# E-21_DEBUG_RTC_USB_A_CAN.net
KiCad netlist of a schematic drawn in Altium Designer
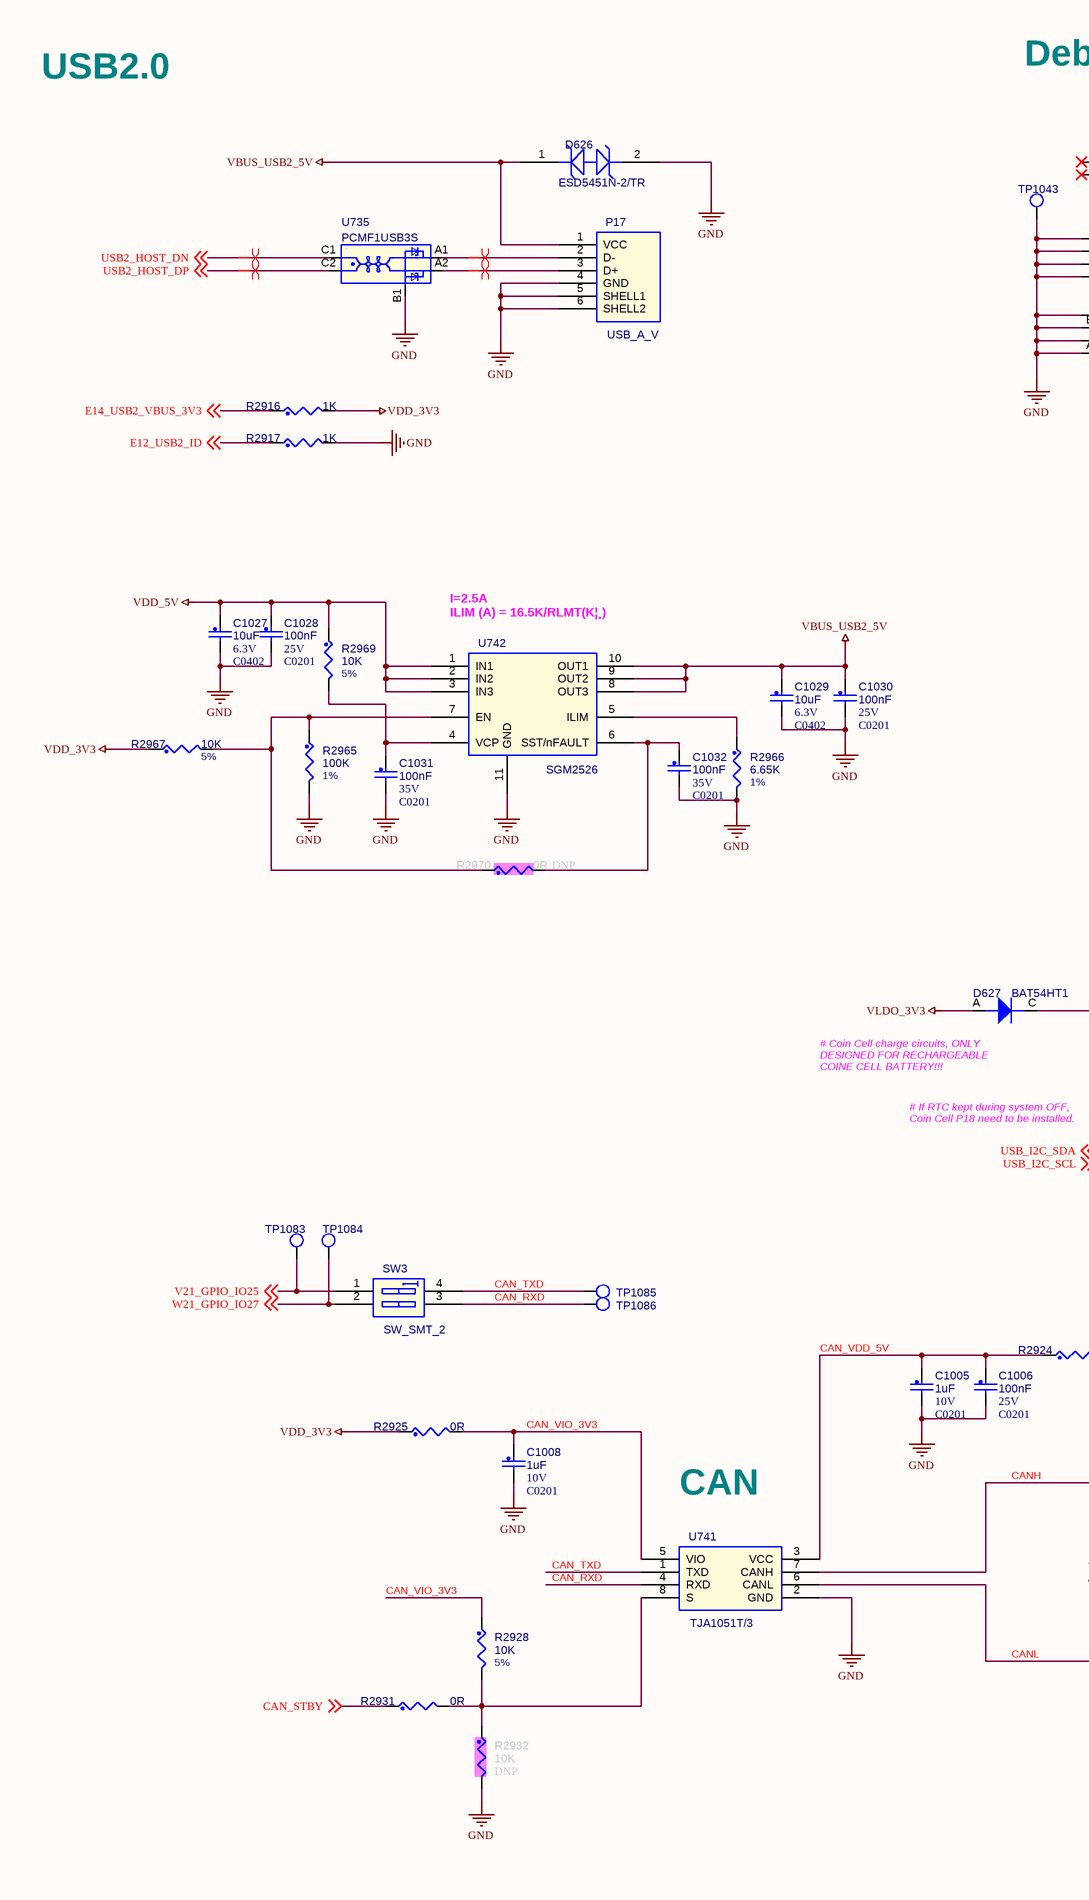
[diagram p0: E-21 DEBUG_RTC_USB A_CAN.SchDoc, left]
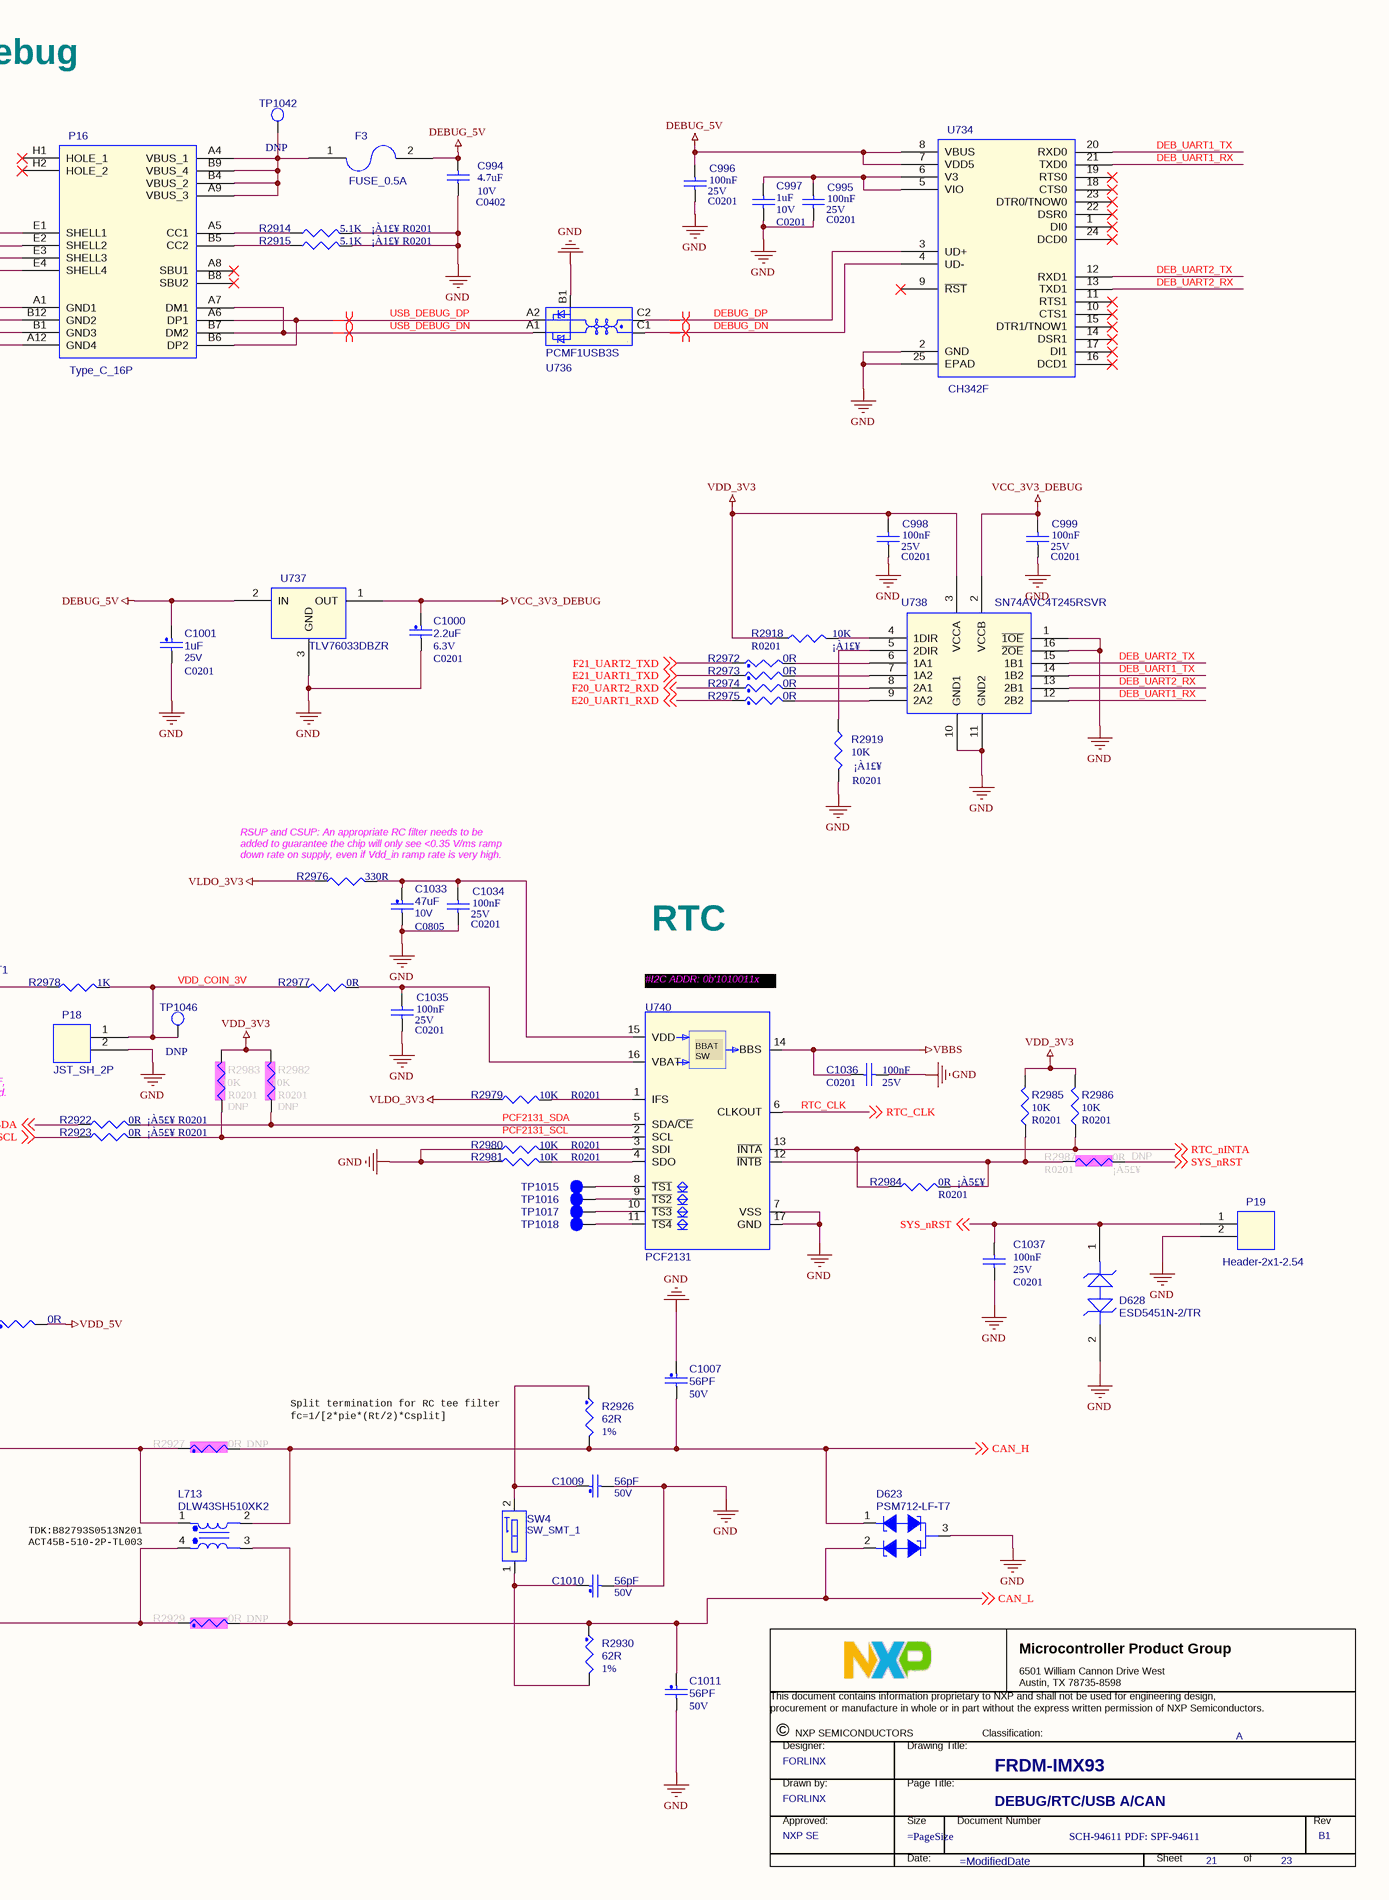
[diagram p1: E-21 DEBUG_RTC_USB A_CAN.SchDoc, right]

(export (version "E")
  (design (tool "Eeschema 10.0.6"))
  (components
    (comp (ref "C994")
      (value "4.7uF")
      (footprint "C0402")
      (description "0402,4.7uF,10V,+/-10%,X5R")
      (fields (field (name "VOLTAGE") "10V") (field (name "PCB FOOTPRINT") "C0402"))
      (libsource (lib "*") (part "C0603,4.7uF"))
    )
    (comp (ref "C995")
      (value "100nF")
      (footprint "C0201")
      (description "0201,100nF,25V,+/-10%,X5R")
      (fields (field (name "PCB FOOTPRINT") "C0201") (field (name "VOLTAGE") "25V"))
      (libsource (lib "*") (part "C0402,100nF,16V"))
    )
    (comp (ref "C996")
      (value "100nF")
      (footprint "C0201")
      (description "0201,100nF,25V,+/-10%,X5R")
      (fields (field (name "PCB FOOTPRINT") "C0201") (field (name "VOLTAGE") "25V"))
      (libsource (lib "*") (part "C0402,100nF,16V"))
    )
    (comp (ref "C997")
      (value "1uF")
      (footprint "C0201")
      (description "0201,1uF,10V,+/-20%,X5R")
      (fields (field (name "PCB FOOTPRINT") "C0201") (field (name "VOLTAGE") "10V"))
      (libsource (lib "*") (part "C0402,1uF,16V"))
    )
    (comp (ref "C998")
      (value "100nF")
      (footprint "C0201")
      (description "0201,100nF,25V,+/-10%,X5R")
      (fields (field (name "PCB FOOTPRINT") "C0201") (field (name "VOLTAGE") "25V"))
      (libsource (lib "*") (part "C0402,100nF,16V"))
    )
    (comp (ref "C999")
      (value "100nF")
      (footprint "C0201")
      (description "0201,100nF,25V,+/-10%,X5R")
      (fields (field (name "PCB FOOTPRINT") "C0201") (field (name "VOLTAGE") "25V"))
      (libsource (lib "*") (part "C0402,100nF,16V"))
    )
    (comp (ref "C1000")
      (value "2.2uF")
      (footprint "C0201")
      (description "0201,2.2uf,6.3V,+/-20%,X5R")
      (fields
        (field (name "TOLERANCE") "10%")
        (field (name "VOLTAGE") "6.3V")
        (field (name "PCB FOOTPRINT") "C0201")
      )
      (libsource (lib "*") (part "CAP_NP"))
    )
    (comp (ref "C1001")
      (value "1uF")
      (footprint "C0201")
      (description "0201,1uF,10V,+/-20%,X5R")
      (fields
        (field (name "RATED VOLTAGE") "25V")
        (field (name "TOLERANCE") "10%")
        (field (name "PCB FOOTPRINT") "C0201")
      )
      (libsource (lib "*") (part "CAP_NP"))
    )
    (comp (ref "C1005")
      (value "1uF")
      (footprint "C0201")
      (description "0201,1uF,10V,+/-20%,X5R")
      (fields
        (field (name "VOLTAGE") "10V")
        (field (name "TOLERANCE") "10%")
        (field (name "PCB FOOTPRINT") "C0201")
      )
      (libsource (lib "*") (part "CAP_NP"))
    )
    (comp (ref "C1006")
      (value "100nF")
      (footprint "C0201")
      (description "0201,100nF,25V,+/-10%,X5R")
      (fields
        (field (name "TOLERANCE") "10%")
        (field (name "VOLTAGE") "25V")
        (field (name "PCB FOOTPRINT") "C0201")
      )
      (libsource (lib "*") (part "CAP_NP"))
    )
    (comp (ref "C1007")
      (value "56PF")
      (footprint "C0402")
      (description "0402,56pF,50V,+/-5%,COG")
      (fields (field (name "TOLERANCE") "5%") (field (name "VOLTAGE") "50V"))
      (libsource (lib "*") (part "CAP_NP"))
    )
    (comp (ref "C1008")
      (value "1uF")
      (footprint "C0201")
      (description "0201,1uF,10V,+/-20%,X5R")
      (fields
        (field (name "VOLTAGE") "10V")
        (field (name "TOLERANCE") "10%")
        (field (name "PCB FOOTPRINT") "C0201")
      )
      (libsource (lib "*") (part "CAP_NP"))
    )
    (comp (ref "C1009")
      (value "56pF")
      (footprint "C0402")
      (description "0402,56pF,50V,+/-5%,COG")
      (fields (field (name "TOLERANCE") "5%") (field (name "VOLTAGE") "50V"))
      (libsource (lib "*") (part "CAP_NP"))
    )
    (comp (ref "C1010")
      (value "56pF")
      (footprint "C0402")
      (description "0402,56pF,50V,+/-5%,COG")
      (fields (field (name "VOLTAGE") "50V") (field (name "TOLERANCE") "5%"))
      (libsource (lib "*") (part "CAP_NP"))
    )
    (comp (ref "C1011")
      (value "56PF")
      (footprint "C0402")
      (description "0402,56pF,50V,+/-5%,COG")
      (fields (field (name "VOLTAGE") "50V") (field (name "TOLERANCE") "5%"))
      (libsource (lib "*") (part "CAP_NP"))
    )
    (comp (ref "C1027")
      (value "10uF")
      (footprint "C0402")
      (description "0402,10uF,6.3V,+/-20%,X5R")
      (fields
        (field (name "VOLTAGE") "6.3V")
        (field (name "TOLERANCE") "20%")
        (field (name "PCB FOOTPRINT") "C0402")
      )
      (libsource (lib "*") (part "CAP_NP"))
    )
    (comp (ref "C1028")
      (value "100nF")
      (footprint "C0201")
      (description "0201,100nF,25V,+/-10%,X5R")
      (fields
        (field (name "TOLERANCE") "10%")
        (field (name "VOLTAGE") "25V")
        (field (name "PCB FOOTPRINT") "C0201")
      )
      (libsource (lib "*") (part "CAP_NP"))
    )
    (comp (ref "C1029")
      (value "10uF")
      (footprint "C0402")
      (description "0402,10uF,6.3V,+/-20%,X5R")
      (fields
        (field (name "TOLERANCE") "20%")
        (field (name "VOLTAGE") "6.3V")
        (field (name "PCB FOOTPRINT") "C0402")
      )
      (libsource (lib "*") (part "CAP_NP"))
    )
    (comp (ref "C1030")
      (value "100nF")
      (footprint "C0201")
      (description "0201,100nF,25V,+/-10%,X5R")
      (fields
        (field (name "VOLTAGE") "25V")
        (field (name "TOLERANCE") "10%")
        (field (name "PCB FOOTPRINT") "C0201")
      )
      (libsource (lib "*") (part "CAP_NP"))
    )
    (comp (ref "C1031")
      (value "100nF")
      (footprint "C0201")
      (description "0201,100nF,25V,+/-10%,X5R")
      (fields
        (field (name "TOLERANCE") "10%")
        (field (name "VOLTAGE") "35V")
        (field (name "PCB FOOTPRINT") "C0201")
      )
      (libsource (lib "*") (part "CAP_NP"))
    )
    (comp (ref "C1032")
      (value "100nF")
      (footprint "C0201")
      (description "0201,100nF,25V,+/-10%,X5R")
      (fields
        (field (name "TOLERANCE") "10%")
        (field (name "VOLTAGE") "35V")
        (field (name "PCB FOOTPRINT") "C0201")
      )
      (libsource (lib "*") (part "CAP_NP"))
    )
    (comp (ref "C1033")
      (value "47uF")
      (footprint "C0805")
      (description "0805,47uF,10V,+/-20%,X5R")
      (fields
        (field (name "TOLERANCE") "10%")
        (field (name "RATED VOLTAGE") "10V")
        (field (name "PCB FOOTPRINT") "C0805")
      )
      (libsource (lib "*") (part "CAP_NP"))
    )
    (comp (ref "C1034")
      (value "100nF")
      (footprint "C0201")
      (description "0201,100nF,25V,+/-10%,X5R")
      (fields (field (name "PCB FOOTPRINT") "C0201") (field (name "VOLTAGE") "25V"))
      (libsource (lib "*") (part "C0402,100nF,16V"))
    )
    (comp (ref "C1035")
      (value "100nF")
      (footprint "C0201")
      (description "0201,100nF,25V,+/-10%,X5R")
      (fields (field (name "PCB FOOTPRINT") "C0201") (field (name "VOLTAGE") "25V"))
      (libsource (lib "*") (part "C0402,100nF,16V"))
    )
    (comp (ref "C1036")
      (value "100nF")
      (footprint "C0201")
      (description "0201,100nF,25V,+/-10%,X5R")
      (fields (field (name "PCB FOOTPRINT") "C0201") (field (name "VOLTAGE") "25V"))
      (libsource (lib "*") (part "C0402,100nF,16V"))
    )
    (comp (ref "C1037")
      (value "100nF")
      (footprint "C0201")
      (description "0201,100nF,25V,+/-10%,X5R")
      (fields (field (name "PCB FOOTPRINT") "C0201") (field (name "VOLTAGE") "25V"))
      (libsource (lib "*") (part "C0402,100nF,16V"))
    )
    (comp (ref "D623")
      (value "PSM712-LF-T7")
      (footprint "sot23_a")
      (description "PSM712-LF-T7,SOT-23-3")
      (libsource (lib "*") (part "ESD_DIODE_2LINE"))
    )
    (comp (ref "D626")
      (value "ESD5451N-2/TR")
      (footprint "0402TVS")
      (libsource (lib "*") (part "ESD5451N-2/TR"))
    )
    (comp (ref "D627")
      (value "BAT54HT1")
      (footprint "SOD323")
      (description "BAT54HT1G,SOD323")
      (libsource (lib "*") (part "DIODE"))
    )
    (comp (ref "D628")
      (value "ESD5451N-2/TR")
      (footprint "0402TVS")
      (libsource (lib "*") (part "ESD5451N-2/TR"))
    )
    (comp (ref "F3")
      (value "FUSE_0.5A")
      (footprint "F1206")
      (description "1206,0.5A/1A,13.2V")
      (libsource (lib "*") (part "FUSE_0.5A"))
    )
    (comp (ref "L713")
      (value "DLW43SH510XK2")
      (footprint "IND_DLW43")
      (description "IND CHK 51uH@1MHZ 230mA -30%/+50% 1812")
      (libsource (lib "*") (part "DLW43"))
    )
    (comp (ref "P16")
      (value "Type_C_16P")
      (footprint "TypeC_16P_S")
      (description "USB616FC-C2014216,USB2.0,type-c")
      (libsource (lib "*") (part "Type_C_16P"))
    )
    (comp (ref "P17")
      (value "USB_A_V")
      (footprint "USB_A_V")
      (description "USB2.0,Type A, female seat, single-layer, vertical lying, short body, length 14mm")
      (libsource (lib "*") (part "USB_A_V"))
    )
    (comp (ref "P18")
      (value "JST_SH_2P")
      (footprint "sh_2p")
      (description "A1001-02AB,Tin plating, busbar, 2P, 1mm spacing, vertical mounting")
      (libsource (lib "*") (part "JST_SH_2P"))
    )
    (comp (ref "P19")
      (value "Header-2x1-2.54")
      (footprint "Header_2x1_254")
      (description "XH,2P,2.54mm,S")
      (libsource (lib "*") (part "Header-2x1-2.54"))
    )
    (comp (ref "R2914")
      (value "5.1K")
      (footprint "R0201")
      (description "0201,5.1K,+/-1%")
      (fields (field (name "PCB FOOTPRINT") "R0201") (field (name "PRECISION") "±1％"))
      (libsource (lib "*") (part "R0402,4.7K"))
    )
    (comp (ref "R2915")
      (value "5.1K")
      (footprint "R0201")
      (description "0201,5.1K,+/-1%")
      (fields (field (name "PCB FOOTPRINT") "R0201") (field (name "PRECISION") "±1％"))
      (libsource (lib "*") (part "R0402,4.7K"))
    )
    (comp (ref "R2916")
      (value "1K")
      (footprint "R0201")
      (description "0201,1K,+/-1%")
      (fields (field (name "VOLTAGE") "1/16W") (field (name "TOLERANCE") "5%"))
      (libsource (lib "*") (part "RES"))
    )
    (comp (ref "R2917")
      (value "1K")
      (footprint "R0201")
      (description "0201,1K,+/-1%")
      (fields (field (name "VOLTAGE") "1/16W") (field (name "TOLERANCE") "5%"))
      (libsource (lib "*") (part "RES"))
    )
    (comp (ref "R2918")
      (value "10K")
      (footprint "R0201")
      (description "0201,10K,+/-5%")
      (fields (field (name "PRECISION") "±1％") (field (name "PCB FOOTPRINT") "R0201"))
      (libsource (lib "*") (part "R0402,10K"))
    )
    (comp (ref "R2919")
      (value "10K")
      (footprint "R0201")
      (description "0201,10K,+/-5%")
      (fields (field (name "PRECISION") "±1％") (field (name "PCB FOOTPRINT") "R0201"))
      (libsource (lib "*") (part "R0402,10K"))
    )
    (comp (ref "R2922")
      (value "0R")
      (footprint "R0201")
      (description "0201,0Ohm,+/-5%")
      (fields (field (name "PRECISION") "±5％") (field (name "PCB FOOTPRINT") "R0201"))
      (libsource (lib "*") (part "R0402,0R"))
    )
    (comp (ref "R2923")
      (value "0R")
      (footprint "R0201")
      (description "0201,0Ohm,+/-5%")
      (fields (field (name "PRECISION") "±5％") (field (name "PCB FOOTPRINT") "R0201"))
      (libsource (lib "*") (part "R0402,0R"))
    )
    (comp (ref "R2924")
      (value "0R")
      (footprint "R0402")
      (description "0402,0Ohm,+/-1%")
      (fields (field (name "TOLERANCE") "5%") (field (name "VOLTAGE") "1/16W"))
      (libsource (lib "*") (part "RES"))
    )
    (comp (ref "R2925")
      (value "0R")
      (footprint "R0402")
      (description "0402,0Ohm,+/-1%")
      (fields (field (name "VOLTAGE") "1/16W") (field (name "TOLERANCE") "5%"))
      (libsource (lib "*") (part "RES"))
    )
    (comp (ref "R2926")
      (value "62R")
      (footprint "R0603")
      (description "0603,62Ohm,+/-5%")
      (fields (field (name "TOLERANCE") "1%"))
      (libsource (lib "*") (part "RES"))
    )
    (comp (ref "R2927")
      (value "0R")
      (footprint "R0402")
      (description "0402,0Ohm,+/-1%")
      (fields
        (field (name "ASSY_OPT") "DNP")
        (field (name "TOLERANCE") "5%")
        (field (name "VOLTAGE") "1/16W")
      )
      (libsource (lib "*") (part "RES"))
    )
    (comp (ref "R2928")
      (value "10K")
      (footprint "R0201")
      (description "0201,10K,+/-5%")
      (fields (field (name "TOLERANCE") "5%"))
      (libsource (lib "*") (part "RES"))
    )
    (comp (ref "R2929")
      (value "0R")
      (footprint "R0402")
      (description "0402,0Ohm,+/-1%")
      (fields
        (field (name "ASSY_OPT") "DNP")
        (field (name "TOLERANCE") "5%")
        (field (name "VOLTAGE") "1/16W")
      )
      (libsource (lib "*") (part "RES"))
    )
    (comp (ref "R2930")
      (value "62R")
      (footprint "R0603")
      (description "0603,62Ohm,+/-5%")
      (fields (field (name "TOLERANCE") "1%"))
      (libsource (lib "*") (part "RES"))
    )
    (comp (ref "R2931")
      (value "0R")
      (footprint "R0201")
      (description "0201,0Ohm,+/-5%")
      (fields (field (name "VOLTAGE") "1/16W") (field (name "TOLERANCE") "5%"))
      (libsource (lib "*") (part "RES"))
    )
    (comp (ref "R2932")
      (value "10K")
      (footprint "R0201")
      (description "0201,10K,+/-5%")
      (fields (field (name "ASSY_OPT") "DNP") (field (name "TOLERANCE") "5%"))
      (libsource (lib "*") (part "RES"))
    )
    (comp (ref "R2965")
      (value "100K")
      (footprint "R0201")
      (description "0201,100K,+/-1%")
      (fields (field (name "TOLERANCE") "1%"))
      (libsource (lib "*") (part "RES"))
    )
    (comp (ref "R2966")
      (value "6.65K")
      (footprint "R0402")
      (description "0402,6.65K,+/-1%")
      (fields (field (name "TOLERANCE") "1%"))
      (libsource (lib "*") (part "RES"))
    )
    (comp (ref "R2967")
      (value "10K")
      (footprint "R0201")
      (description "0201,10K,+/-5%")
      (fields (field (name "TOLERANCE") "5%"))
      (libsource (lib "*") (part "RES"))
    )
    (comp (ref "R2969")
      (value "10K")
      (footprint "R0201")
      (description "0201,10K,+/-5%")
      (fields (field (name "TOLERANCE") "5%"))
      (libsource (lib "*") (part "RES"))
    )
    (comp (ref "R2970")
      (value "0R")
      (footprint "R0201")
      (description "0201,0Ohm,+/-5%")
      (fields
        (field (name "ASSY_OPT") "DNP")
        (field (name "VOLTAGE") "1/16W")
        (field (name "TOLERANCE") "5%")
      )
      (libsource (lib "*") (part "RES"))
    )
    (comp (ref "R2972")
      (value "0R")
      (footprint "R0201")
      (description "0201,0Ohm,+/-5%")
      (fields (field (name "TOLERANCE") "5%") (field (name "VOLTAGE") "1/16W"))
      (libsource (lib "*") (part "RES"))
    )
    (comp (ref "R2973")
      (value "0R")
      (footprint "R0201")
      (description "0201,0Ohm,+/-5%")
      (fields (field (name "TOLERANCE") "5%") (field (name "VOLTAGE") "1/16W"))
      (libsource (lib "*") (part "RES"))
    )
    (comp (ref "R2974")
      (value "0R")
      (footprint "R0201")
      (description "0201,0Ohm,+/-5%")
      (fields (field (name "TOLERANCE") "5%") (field (name "VOLTAGE") "1/16W"))
      (libsource (lib "*") (part "RES"))
    )
    (comp (ref "R2975")
      (value "0R")
      (footprint "R0201")
      (description "0201,0Ohm,+/-5%")
      (fields (field (name "TOLERANCE") "5%") (field (name "VOLTAGE") "1/16W"))
      (libsource (lib "*") (part "RES"))
    )
    (comp (ref "R2976")
      (value "330R")
      (footprint "R0402")
      (description "0402,330Ohm,+/-1%")
      (libsource (lib "*") (part "R0402,10K"))
    )
    (comp (ref "R2977")
      (value "0R")
      (footprint "R0402")
      (description "0402,0Ohm,+/-1%")
      (libsource (lib "*") (part "R0402,10K"))
    )
    (comp (ref "R2978")
      (value "1K")
      (footprint "R0402")
      (description "0402,1K,+/-1%")
      (libsource (lib "*") (part "R0402,10K"))
    )
    (comp (ref "R2979")
      (value "10K")
      (footprint "R0201")
      (description "0201,10K,+/-5%")
      (fields (field (name "PCB FOOTPRINT") "R0201"))
      (libsource (lib "*") (part "R0402,10K"))
    )
    (comp (ref "R2980")
      (value "10K")
      (footprint "R0201")
      (description "0201,10K,+/-5%")
      (fields (field (name "PCB FOOTPRINT") "R0201"))
      (libsource (lib "*") (part "R0402,10K"))
    )
    (comp (ref "R2981")
      (value "10K")
      (footprint "R0201")
      (description "0201,10K,+/-5%")
      (fields (field (name "PCB FOOTPRINT") "R0201"))
      (libsource (lib "*") (part "R0402,10K"))
    )
    (comp (ref "R2982")
      (value "10K")
      (footprint "R0201")
      (description "0201,10K,+/-5%")
      (fields (field (name "PCB FOOTPRINT") "R0201") (field (name "ASSY_OPT") "DNP"))
      (libsource (lib "*") (part "R0402,10K"))
    )
    (comp (ref "R2983")
      (value "10K")
      (footprint "R0201")
      (description "0201,10K,+/-5%")
      (fields (field (name "PCB FOOTPRINT") "R0201") (field (name "ASSY_OPT") "DNP"))
      (libsource (lib "*") (part "R0402,10K"))
    )
    (comp (ref "R2984")
      (value "0R")
      (footprint "R0201")
      (description "0201,0Ohm,+/-5%")
      (fields (field (name "PRECISION") "±5％") (field (name "PCB FOOTPRINT") "R0201"))
      (libsource (lib "*") (part "R0402,0R"))
    )
    (comp (ref "R2985")
      (value "10K")
      (footprint "R0201")
      (description "0201,10K,+/-5%")
      (fields (field (name "PCB FOOTPRINT") "R0201"))
      (libsource (lib "*") (part "R0402,10K"))
    )
    (comp (ref "R2986")
      (value "10K")
      (footprint "R0201")
      (description "0201,10K,+/-5%")
      (fields (field (name "PCB FOOTPRINT") "R0201"))
      (libsource (lib "*") (part "R0402,10K"))
    )
    (comp (ref "R2987")
      (value "0R")
      (footprint "R0201")
      (description "0201,0Ohm,+/-5%")
      (fields
        (field (name "PRECISION") "±5％")
        (field (name "PCB FOOTPRINT") "R0201")
        (field (name "ASSY_OPT") "DNP")
      )
      (libsource (lib "*") (part "R0402,0R"))
    )
    (comp (ref "SW3")
      (value "SW_SMT_2")
      (footprint "SW_SMT_4")
      (description "2bit,4P,1.27mm,black")
      (libsource (lib "*") (part "SW_SMT_1"))
    )
    (comp (ref "SW4")
      (value "SW_SMT_1")
      (footprint "sw_2p8x5p4_sm")
      (description "1bit,2P,1.27mm,black")
      (libsource (lib "*") (part "SW-SPST_A"))
    )
    (comp (ref "TP1015")
      (value "TPAD_015")
      (footprint "tpad_015")
      (description "no part to order")
      (libsource (lib "*") (part "TESTLOOP"))
    )
    (comp (ref "TP1016")
      (value "TPAD_015")
      (footprint "tpad_015")
      (description "no part to order")
      (libsource (lib "*") (part "TESTLOOP"))
    )
    (comp (ref "TP1017")
      (value "TPAD_015")
      (footprint "tpad_015")
      (description "no part to order")
      (libsource (lib "*") (part "TESTLOOP"))
    )
    (comp (ref "TP1018")
      (value "TPAD_015")
      (footprint "tpad_015")
      (description "no part to order")
      (libsource (lib "*") (part "TESTLOOP"))
    )
    (comp (ref "TP1042")
      (value "TPAD_020")
      (footprint "tpad_020")
      (description "no part to order")
      (fields (field (name "ASSY_OPT") "DNP"))
      (libsource (lib "*") (part "T POINT R"))
    )
    (comp (ref "TP1043")
      (value "TPAD_020")
      (footprint "tpad_020")
      (description "no part to order")
      (libsource (lib "*") (part "T POINT R"))
    )
    (comp (ref "TP1046")
      (value "TPAD_020")
      (footprint "tpad_020")
      (description "no part to order")
      (fields (field (name "ASSY_OPT") "DNP"))
      (libsource (lib "*") (part "T POINT R"))
    )
    (comp (ref "TP1083")
      (value "TPAD_020")
      (footprint "tpad_020")
      (description "no part to order")
      (libsource (lib "*") (part "T POINT R"))
    )
    (comp (ref "TP1084")
      (value "TPAD_020")
      (footprint "tpad_020")
      (description "no part to order")
      (libsource (lib "*") (part "T POINT R"))
    )
    (comp (ref "TP1085")
      (value "TPAD_020")
      (footprint "tpad_020")
      (description "no part to order")
      (libsource (lib "*") (part "T POINT R"))
    )
    (comp (ref "TP1086")
      (value "TPAD_020")
      (footprint "tpad_020")
      (description "no part to order")
      (libsource (lib "*") (part "T POINT R"))
    )
    (comp (ref "U734") (value "CH342F") (footprint "QFN24P_0_5") (libsource (lib "*") (part "CH342F")))
    (comp (ref "U735")
      (value "PCMF1USB3S")
      (footprint "wlcsp5_0p4_0p82x1p22")
      (description "IC EMI FILTER ESD PROTECTION 15kV/LINE WLCSP5")
      (fields
        (field (name "MANUFACTURER PART NUMBER") "PESD1USB30")
        (field (name "MANUFACTURER") "NXP Semiconductors")
      )
      (libsource (lib "*") (part "PESD1USB30_5P"))
    )
    (comp (ref "U736")
      (value "PCMF1USB3S")
      (footprint "wlcsp5_0p4_0p82x1p22")
      (description "IC EMI FILTER ESD PROTECTION 15kV/LINE WLCSP5")
      (fields
        (field (name "MANUFACTURER PART NUMBER") "PESD1USB30")
        (field (name "MANUFACTURER") "NXP Semiconductors")
      )
      (libsource (lib "") (part "PESD1USB30_5P_1"))
    )
    (comp (ref "U737")
      (value "TLV76033DBZR")
      (footprint "sot23_a")
      (libsource (lib "*") (part "SGM2034-3_1.3YN3G"))
    )
    (comp (ref "U738")
      (value "SN74AVC4T245RSVR")
      (footprint "UQFN16_26x18")
      (description "SN74AVC4T245RSVR,UQFN16_2.6x1.8mm")
      (libsource (lib "*") (part "SN74AVC4T245RSVR"))
    )
    (comp (ref "U740")
      (value "PCF2131")
      (footprint "so16_0p5_3p5x4p5_mm")
      (description "PCF2131TF,HLSON16,Nano-power highly accurate RTC with integrated quartz crystal")
      (libsource (lib "*") (part "PCF2131_4"))
    )
    (comp (ref "U741")
      (value "TJA1051T/3")
      (footprint "SOP8_1_27")
      (description "TJA1051T/3,SO8")
      (libsource (lib "*") (part "TJA1051T/3"))
    )
    (comp (ref "U742")
      (value "SGM2526")
      (footprint "tdfn_3x3_10l")
      (description "SGM2526YTD10G/TR,TDFN-3x3-10L,-40+C~85+C,Imax 5A")
      (libsource (lib "*") (part "SGM2526_3"))
    )
  )
  (nets
    (net (code "1") (name "/CANH") (class "Default")
      (node (ref "L713") (pin "1") (pinfunction "1_1") (pintype "passive"))
      (node (ref "R2927") (pin "1") (pinfunction "1_1") (pintype "passive"))
      (node (ref "U741") (pin "7") (pinfunction "CANH_7") (pintype "passive"))
    )
    (net (code "2") (name "/CANL") (class "Default")
      (node (ref "L713") (pin "4") (pinfunction "4_4") (pintype "passive"))
      (node (ref "R2929") (pin "1") (pinfunction "1_1") (pintype "passive"))
      (node (ref "U741") (pin "6") (pinfunction "CANL_6") (pintype "passive"))
    )
    (net (code "3") (name "/CAN_RXD") (class "Default")
      (node (ref "SW3") (pin "3") (pinfunction "3_3") (pintype "passive"))
      (node (ref "TP1086") (pin "1") (pinfunction "TP_1") (pintype "passive"))
      (node (ref "U741") (pin "4") (pinfunction "RXD_4") (pintype "passive"))
    )
    (net (code "4") (name "/CAN_TXD") (class "Default")
      (node (ref "SW3") (pin "4") (pinfunction "4_4") (pintype "passive"))
      (node (ref "TP1085") (pin "1") (pinfunction "TP_1") (pintype "passive"))
      (node (ref "U741") (pin "1") (pinfunction "TXD_1") (pintype "passive"))
    )
    (net (code "5") (name "/CAN_VDD_5V") (class "Default")
      (node (ref "C1005") (pin "1") (pinfunction "1_1") (pintype "passive"))
      (node (ref "C1006") (pin "1") (pinfunction "1_1") (pintype "passive"))
      (node (ref "R2924") (pin "1") (pinfunction "1_1") (pintype "passive"))
      (node (ref "U741") (pin "3") (pinfunction "VCC_3") (pintype "passive"))
    )
    (net (code "6") (name "/CAN_VIO_3V3") (class "Default")
      (node (ref "C1008") (pin "1") (pinfunction "1_1") (pintype "passive"))
      (node (ref "R2925") (pin "2") (pinfunction "2_2") (pintype "passive"))
      (node (ref "R2928") (pin "1") (pinfunction "1_1") (pintype "passive"))
      (node (ref "U741") (pin "5") (pinfunction "VIO_5") (pintype "passive"))
    )
    (net (code "7") (name "/DEBUG_DN") (class "Default")
      (node (ref "U734") (pin "4") (pinfunction "UD-_4") (pintype "passive"))
      (node (ref "U736") (pin "C1") (pinfunction "CH1_OUT+_C1") (pintype "bidirectional"))
    )
    (net (code "8") (name "/DEBUG_DP") (class "Default")
      (node (ref "U734") (pin "3") (pinfunction "UD+_3") (pintype "passive"))
      (node (ref "U736") (pin "C2") (pinfunction "CH1_OUT-_C2") (pintype "bidirectional"))
    )
    (net (code "9") (name "/DEB_UART1_RX") (class "Default")
      (node (ref "U734") (pin "21") (pinfunction "TXD0_21") (pintype "passive"))
      (node (ref "U738") (pin "12") (pinfunction "2B2_12") (pintype "passive"))
    )
    (net (code "10") (name "/DEB_UART1_TX") (class "Default")
      (node (ref "U734") (pin "20") (pinfunction "RXD0_20") (pintype "passive"))
      (node (ref "U738") (pin "14") (pinfunction "1B2_14") (pintype "passive"))
    )
    (net (code "11") (name "/DEB_UART2_RX") (class "Default")
      (node (ref "U734") (pin "13") (pinfunction "TXD1_13") (pintype "passive"))
      (node (ref "U738") (pin "13") (pinfunction "2B1_13") (pintype "passive"))
    )
    (net (code "12") (name "/DEB_UART2_TX") (class "Default")
      (node (ref "U734") (pin "12") (pinfunction "RXD1_12") (pintype "passive"))
      (node (ref "U738") (pin "15") (pinfunction "1B1_15") (pintype "passive"))
    )
    (net (code "13") (name "/PCF2131_SCL") (class "Default")
      (node (ref "R2923") (pin "2") (pinfunction "2_2") (pintype "passive"))
      (node (ref "R2983") (pin "1") (pinfunction "1_1") (pintype "passive"))
      (node (ref "U740") (pin "2") (pinfunction "SCL_2") (pintype "passive"))
    )
    (net (code "14") (name "/PCF2131_SDA") (class "Default")
      (node (ref "R2922") (pin "2") (pinfunction "2_2") (pintype "passive"))
      (node (ref "R2982") (pin "1") (pinfunction "1_1") (pintype "passive"))
      (node (ref "U740") (pin "5") (pinfunction "SDA/~{CE}_5") (pintype "passive"))
    )
    (net (code "15") (name "/USB_DEBUG_DN") (class "Default")
      (node (ref "P16") (pin "A7") (pinfunction "DM1_A7") (pintype "passive"))
      (node (ref "P16") (pin "B7") (pinfunction "DM2_B7") (pintype "passive"))
      (node (ref "U736") (pin "A1") (pinfunction "CH1_IN+_A1") (pintype "bidirectional"))
    )
    (net (code "16") (name "/USB_DEBUG_DP") (class "Default")
      (node (ref "P16") (pin "A6") (pinfunction "DP1_A6") (pintype "passive"))
      (node (ref "P16") (pin "B6") (pinfunction "DP2_B6") (pintype "passive"))
      (node (ref "U736") (pin "A2") (pinfunction "CH1_IN-_A2") (pintype "bidirectional"))
    )
    (net (code "17") (name "/VDD_COIN_3V") (class "Default")
      (node (ref "P18") (pin "1") (pinfunction "1_1") (pintype "passive"))
      (node (ref "R2977") (pin "1") (pinfunction "1_1") (pintype "passive"))
      (node (ref "R2978") (pin "2") (pinfunction "2_2") (pintype "passive"))
      (node (ref "TP1046") (pin "1") (pinfunction "TP_1") (pintype "passive"))
    )
    (net (code "18") (name "CAN_H") (class "Default")
      (node (ref "C1007") (pin "2") (pinfunction "2_2") (pintype "passive"))
      (node (ref "D623") (pin "1") (pinfunction "CATHODE1_1") (pintype "passive"))
      (node (ref "L713") (pin "2") (pinfunction "2_2") (pintype "passive"))
      (node (ref "R2926") (pin "2") (pinfunction "2_2") (pintype "passive"))
      (node (ref "R2927") (pin "2") (pinfunction "2_2") (pintype "passive"))
    )
    (net (code "19") (name "CAN_L") (class "Default")
      (node (ref "C1011") (pin "1") (pinfunction "1_1") (pintype "passive"))
      (node (ref "D623") (pin "2") (pinfunction "CATHODE2_2") (pintype "passive"))
      (node (ref "L713") (pin "3") (pinfunction "3_3") (pintype "passive"))
      (node (ref "R2929") (pin "2") (pinfunction "2_2") (pintype "passive"))
      (node (ref "R2930") (pin "1") (pinfunction "1_1") (pintype "passive"))
    )
    (net (code "20") (name "CAN_STBY") (class "Default")
      (node (ref "R2931") (pin "1") (pinfunction "1_1") (pintype "passive"))
    )
    (net (code "21") (name "DEBUG_5V") (class "Default")
      (node (ref "C1001") (pin "1") (pinfunction "1_1") (pintype "passive"))
      (node (ref "C994") (pin "1") (pinfunction "1_1") (pintype "passive"))
      (node (ref "C996") (pin "1") (pinfunction "1_1") (pintype "passive"))
      (node (ref "F3") (pin "2") (pinfunction "2_2") (pintype "passive"))
      (node (ref "U734") (pin "7") (pinfunction "VDD5_7") (pintype "passive"))
      (node (ref "U734") (pin "8") (pinfunction "VBUS_8") (pintype "passive"))
      (node (ref "U737") (pin "2") (pinfunction "IN_2") (pintype "passive"))
    )
    (net (code "22") (name "E12_USB2_ID") (class "Default")
      (node (ref "R2917") (pin "1") (pinfunction "1_1") (pintype "passive"))
    )
    (net (code "23") (name "E14_USB2_VBUS_3V3") (class "Default")
      (node (ref "R2916") (pin "1") (pinfunction "1_1") (pintype "passive"))
    )
    (net (code "24") (name "E20_UART1_RXD") (class "Default")
      (node (ref "R2975") (pin "1") (pinfunction "1_1") (pintype "passive"))
    )
    (net (code "25") (name "E21_UART1_TXD") (class "Default")
      (node (ref "R2973") (pin "1") (pinfunction "1_1") (pintype "passive"))
    )
    (net (code "26") (name "F20_UART2_RXD") (class "Default")
      (node (ref "R2974") (pin "1") (pinfunction "1_1") (pintype "passive"))
    )
    (net (code "27") (name "F21_UART2_TXD") (class "Default")
      (node (ref "R2972") (pin "1") (pinfunction "1_1") (pintype "passive"))
    )
    (net (code "28") (name "GND") (class "Default")
      (node (ref "C1000") (pin "2") (pinfunction "2_2") (pintype "passive"))
      (node (ref "C1001") (pin "2") (pinfunction "2_2") (pintype "passive"))
      (node (ref "C1005") (pin "2") (pinfunction "2_2") (pintype "passive"))
      (node (ref "C1006") (pin "2") (pinfunction "2_2") (pintype "passive"))
      (node (ref "C1007") (pin "1") (pinfunction "1_1") (pintype "passive"))
      (node (ref "C1008") (pin "2") (pinfunction "2_2") (pintype "passive"))
      (node (ref "C1009") (pin "2") (pinfunction "2_2") (pintype "passive"))
      (node (ref "C1010") (pin "2") (pinfunction "2_2") (pintype "passive"))
      (node (ref "C1011") (pin "2") (pinfunction "2_2") (pintype "passive"))
      (node (ref "C1027") (pin "2") (pinfunction "2_2") (pintype "passive"))
      (node (ref "C1028") (pin "2") (pinfunction "2_2") (pintype "passive"))
      (node (ref "C1029") (pin "2") (pinfunction "2_2") (pintype "passive"))
      (node (ref "C1030") (pin "2") (pinfunction "2_2") (pintype "passive"))
      (node (ref "C1031") (pin "2") (pinfunction "2_2") (pintype "passive"))
      (node (ref "C1032") (pin "2") (pinfunction "2_2") (pintype "passive"))
      (node (ref "C1033") (pin "2") (pinfunction "2_2") (pintype "passive"))
      (node (ref "C1034") (pin "2") (pinfunction "2_2") (pintype "passive"))
      (node (ref "C1035") (pin "2") (pinfunction "2_2") (pintype "passive"))
      (node (ref "C1036") (pin "2") (pinfunction "2_2") (pintype "passive"))
      (node (ref "C1037") (pin "1") (pinfunction "1_1") (pintype "passive"))
      (node (ref "C994") (pin "2") (pinfunction "2_2") (pintype "passive"))
      (node (ref "C995") (pin "2") (pinfunction "2_2") (pintype "passive"))
      (node (ref "C996") (pin "2") (pinfunction "2_2") (pintype "passive"))
      (node (ref "C997") (pin "2") (pinfunction "2_2") (pintype "passive"))
      (node (ref "C998") (pin "2") (pinfunction "2_2") (pintype "passive"))
      (node (ref "C999") (pin "2") (pinfunction "2_2") (pintype "passive"))
      (node (ref "D623") (pin "3") (pinfunction "COM_CATHODE_3") (pintype "passive"))
      (node (ref "D626") (pin "2") (pinfunction "2_2") (pintype "passive"))
      (node (ref "D628") (pin "2") (pinfunction "2_2") (pintype "passive"))
      (node (ref "P16") (pin "A1") (pinfunction "GND1_A1") (pintype "passive"))
      (node (ref "P16") (pin "A12") (pinfunction "GND4_A12") (pintype "passive"))
      (node (ref "P16") (pin "B1") (pinfunction "GND3_B1") (pintype "passive"))
      (node (ref "P16") (pin "B12") (pinfunction "GND2_B12") (pintype "passive"))
      (node (ref "P16") (pin "E1") (pinfunction "SHELL1_E1") (pintype "passive"))
      (node (ref "P16") (pin "E2") (pinfunction "SHELL2_E2") (pintype "passive"))
      (node (ref "P16") (pin "E3") (pinfunction "SHELL3_E3") (pintype "passive"))
      (node (ref "P16") (pin "E4") (pinfunction "SHELL4_E4") (pintype "passive"))
      (node (ref "P17") (pin "4") (pinfunction "GND_4") (pintype "passive"))
      (node (ref "P17") (pin "5") (pinfunction "SHELL1_5") (pintype "passive"))
      (node (ref "P17") (pin "6") (pinfunction "SHELL2_6") (pintype "passive"))
      (node (ref "P18") (pin "2") (pinfunction "2_2") (pintype "passive"))
      (node (ref "P19") (pin "2") (pinfunction "2_2") (pintype "passive"))
      (node (ref "R2914") (pin "2") (pinfunction "2_2") (pintype "passive"))
      (node (ref "R2915") (pin "2") (pinfunction "2_2") (pintype "passive"))
      (node (ref "R2917") (pin "2") (pinfunction "2_2") (pintype "passive"))
      (node (ref "R2919") (pin "2") (pinfunction "2_2") (pintype "passive"))
      (node (ref "R2932") (pin "2") (pinfunction "2_2") (pintype "passive"))
      (node (ref "R2965") (pin "2") (pinfunction "2_2") (pintype "passive"))
      (node (ref "R2966") (pin "2") (pinfunction "2_2") (pintype "passive"))
      (node (ref "R2980") (pin "1") (pinfunction "1_1") (pintype "passive"))
      (node (ref "R2981") (pin "1") (pinfunction "1_1") (pintype "passive"))
      (node (ref "TP1043") (pin "1") (pinfunction "TP_1") (pintype "passive"))
      (node (ref "U734") (pin "2") (pinfunction "GND_2") (pintype "passive"))
      (node (ref "U734") (pin "25") (pinfunction "EPAD_25") (pintype "passive"))
      (node (ref "U735") (pin "B1") (pinfunction "GND_B1") (pintype "power_in"))
      (node (ref "U736") (pin "B1") (pinfunction "GND_B1") (pintype "power_in"))
      (node (ref "U737") (pin "3") (pinfunction "GND_3") (pintype "passive"))
      (node (ref "U738") (pin "1") (pinfunction "~{1OE}_1") (pintype "passive"))
      (node (ref "U738") (pin "10") (pinfunction "GND1_10") (pintype "passive"))
      (node (ref "U738") (pin "11") (pinfunction "GND2_11") (pintype "passive"))
      (node (ref "U738") (pin "16") (pinfunction "~{2OE}_16") (pintype "passive"))
      (node (ref "U740") (pin "17") (pinfunction "GND_17") (pintype "power_in"))
      (node (ref "U740") (pin "7") (pinfunction "VSS_7") (pintype "power_in"))
      (node (ref "U741") (pin "2") (pinfunction "GND_2") (pintype "passive"))
      (node (ref "U742") (pin "11") (pinfunction "GND_11") (pintype "passive"))
    )
    (net (code "29") (name "Net-(D627-CATHODE)") (class "Default")
      (node (ref "D627") (pin "C") (pinfunction "CATHODE_C") (pintype "passive"))
      (node (ref "R2978") (pin "1") (pinfunction "1_1") (pintype "passive"))
    )
    (net (code "30") (name "Net-(P16-CC1)") (class "Default")
      (node (ref "P16") (pin "A5") (pinfunction "CC1_A5") (pintype "passive"))
      (node (ref "R2914") (pin "1") (pinfunction "1_1") (pintype "passive"))
    )
    (net (code "31") (name "Net-(P16-CC2)") (class "Default")
      (node (ref "P16") (pin "B5") (pinfunction "CC2_B5") (pintype "passive"))
      (node (ref "R2915") (pin "1") (pinfunction "1_1") (pintype "passive"))
    )
    (net (code "32") (name "Net-(P16-VBUS_1)") (class "Default")
      (node (ref "F3") (pin "1") (pinfunction "1_1") (pintype "passive"))
      (node (ref "P16") (pin "A4") (pinfunction "VBUS_1_A4") (pintype "passive"))
      (node (ref "P16") (pin "A9") (pinfunction "VBUS_3_A9") (pintype "passive"))
      (node (ref "P16") (pin "B4") (pinfunction "VBUS_2_B4") (pintype "passive"))
      (node (ref "P16") (pin "B9") (pinfunction "VBUS_4_B9") (pintype "passive"))
      (node (ref "TP1042") (pin "1") (pinfunction "TP_1") (pintype "passive"))
    )
    (net (code "33") (name "Net-(P17-D+)") (class "Default")
      (node (ref "P17") (pin "3") (pinfunction "D+_3") (pintype "passive"))
      (node (ref "U735") (pin "A2") (pinfunction "CH1_IN-_A2") (pintype "bidirectional"))
    )
    (net (code "34") (name "Net-(P17-D-)") (class "Default")
      (node (ref "P17") (pin "2") (pinfunction "D-_2") (pintype "passive"))
      (node (ref "U735") (pin "A1") (pinfunction "CH1_IN+_A1") (pintype "bidirectional"))
    )
    (net (code "35") (name "Net-(SW4-COMMON)") (class "Default")
      (node (ref "C1009") (pin "1") (pinfunction "1_1") (pintype "passive"))
      (node (ref "R2926") (pin "1") (pinfunction "1_1") (pintype "passive"))
      (node (ref "SW4") (pin "2") (pinfunction "COMMON_2") (pintype "passive"))
    )
    (net (code "36") (name "Net-(SW4-NC)") (class "Default")
      (node (ref "C1010") (pin "1") (pinfunction "1_1") (pintype "passive"))
      (node (ref "R2930") (pin "2") (pinfunction "2_2") (pintype "passive"))
      (node (ref "SW4") (pin "1") (pinfunction "NC_1") (pintype "passive"))
    )
    (net (code "37") (name "Net-(TP1015-Pin1)") (class "Default")
      (node (ref "TP1015") (pin "1") (pinfunction "Pin1_1") (pintype "passive"))
      (node (ref "U740") (pin "8") (pinfunction "~{TS1}_8") (pintype "passive"))
    )
    (net (code "38") (name "Net-(TP1016-Pin1)") (class "Default")
      (node (ref "TP1016") (pin "1") (pinfunction "Pin1_1") (pintype "passive"))
      (node (ref "U740") (pin "9") (pinfunction "~{TS2}_9") (pintype "passive"))
    )
    (net (code "39") (name "Net-(TP1017-Pin1)") (class "Default")
      (node (ref "TP1017") (pin "1") (pinfunction "Pin1_1") (pintype "passive"))
      (node (ref "U740") (pin "10") (pinfunction "~{TS3}_10") (pintype "passive"))
    )
    (net (code "40") (name "Net-(TP1018-Pin1)") (class "Default")
      (node (ref "TP1018") (pin "1") (pinfunction "Pin1_1") (pintype "passive"))
      (node (ref "U740") (pin "11") (pinfunction "~{TS4}_11") (pintype "passive"))
    )
    (net (code "41") (name "Net-(U734-V3)") (class "Default")
      (node (ref "C995") (pin "1") (pinfunction "1_1") (pintype "passive"))
      (node (ref "C997") (pin "1") (pinfunction "1_1") (pintype "passive"))
      (node (ref "U734") (pin "5") (pinfunction "VIO_5") (pintype "passive"))
      (node (ref "U734") (pin "6") (pinfunction "V3_6") (pintype "passive"))
    )
    (net (code "42") (name "Net-(U738-1A1)") (class "Default")
      (node (ref "R2972") (pin "2") (pinfunction "2_2") (pintype "passive"))
      (node (ref "U738") (pin "6") (pinfunction "1A1_6") (pintype "passive"))
    )
    (net (code "43") (name "Net-(U738-1A2)") (class "Default")
      (node (ref "R2973") (pin "2") (pinfunction "2_2") (pintype "passive"))
      (node (ref "U738") (pin "7") (pinfunction "1A2_7") (pintype "passive"))
    )
    (net (code "44") (name "Net-(U738-1DIR)") (class "Default")
      (node (ref "R2918") (pin "2") (pinfunction "2_2") (pintype "passive"))
      (node (ref "U738") (pin "4") (pinfunction "1DIR_4") (pintype "passive"))
    )
    (net (code "45") (name "Net-(U738-2A1)") (class "Default")
      (node (ref "R2974") (pin "2") (pinfunction "2_2") (pintype "passive"))
      (node (ref "U738") (pin "8") (pinfunction "2A1_8") (pintype "passive"))
    )
    (net (code "46") (name "Net-(U738-2A2)") (class "Default")
      (node (ref "R2975") (pin "2") (pinfunction "2_2") (pintype "passive"))
      (node (ref "U738") (pin "9") (pinfunction "2A2_9") (pintype "passive"))
    )
    (net (code "47") (name "Net-(U738-2DIR)") (class "Default")
      (node (ref "R2919") (pin "1") (pinfunction "1_1") (pintype "passive"))
      (node (ref "U738") (pin "5") (pinfunction "2DIR_5") (pintype "passive"))
    )
    (net (code "48") (name "Net-(U740-IFS)") (class "Default")
      (node (ref "R2979") (pin "2") (pinfunction "2_2") (pintype "passive"))
      (node (ref "U740") (pin "1") (pinfunction "IFS_1") (pintype "passive"))
    )
    (net (code "49") (name "Net-(U740-SDI)") (class "Default")
      (node (ref "R2980") (pin "2") (pinfunction "2_2") (pintype "passive"))
      (node (ref "U740") (pin "3") (pinfunction "SDI_3") (pintype "passive"))
    )
    (net (code "50") (name "Net-(U740-SDO)") (class "Default")
      (node (ref "R2981") (pin "2") (pinfunction "2_2") (pintype "passive"))
      (node (ref "U740") (pin "4") (pinfunction "SDO_4") (pintype "passive"))
    )
    (net (code "51") (name "Net-(U740-VBAT)") (class "Default")
      (node (ref "C1035") (pin "1") (pinfunction "1_1") (pintype "passive"))
      (node (ref "R2977") (pin "2") (pinfunction "2_2") (pintype "passive"))
      (node (ref "U740") (pin "16") (pinfunction "VBAT_16") (pintype "power_in"))
    )
    (net (code "52") (name "Net-(U740-VDD)") (class "Default")
      (node (ref "C1033") (pin "1") (pinfunction "1_1") (pintype "passive"))
      (node (ref "C1034") (pin "1") (pinfunction "1_1") (pintype "passive"))
      (node (ref "R2976") (pin "2") (pinfunction "2_2") (pintype "passive"))
      (node (ref "U740") (pin "15") (pinfunction "VDD_15") (pintype "power_in"))
    )
    (net (code "53") (name "Net-(U740-~{INTB})") (class "Default")
      (node (ref "R2984") (pin "2") (pinfunction "2_2") (pintype "passive"))
      (node (ref "R2985") (pin "1") (pinfunction "1_1") (pintype "passive"))
      (node (ref "R2987") (pin "1") (pinfunction "1_1") (pintype "passive"))
      (node (ref "U740") (pin "12") (pinfunction "~{INTB}_12") (pintype "passive"))
    )
    (net (code "54") (name "Net-(U741-S)") (class "Default")
      (node (ref "R2928") (pin "2") (pinfunction "2_2") (pintype "passive"))
      (node (ref "R2931") (pin "2") (pinfunction "2_2") (pintype "passive"))
      (node (ref "R2932") (pin "1") (pinfunction "1_1") (pintype "passive"))
      (node (ref "U741") (pin "8") (pinfunction "S_8") (pintype "passive"))
    )
    (net (code "55") (name "Net-(U742-EN)") (class "Default")
      (node (ref "R2965") (pin "1") (pinfunction "1_1") (pintype "passive"))
      (node (ref "R2967") (pin "2") (pinfunction "2_2") (pintype "passive"))
      (node (ref "R2970") (pin "1") (pinfunction "1_1") (pintype "passive"))
      (node (ref "U742") (pin "7") (pinfunction "EN_7") (pintype "passive"))
    )
    (net (code "56") (name "Net-(U742-ILIM)") (class "Default")
      (node (ref "R2966") (pin "1") (pinfunction "1_1") (pintype "passive"))
      (node (ref "U742") (pin "5") (pinfunction "ILIM_5") (pintype "passive"))
    )
    (net (code "57") (name "Net-(U742-SST{slash}nFAULT)") (class "Default")
      (node (ref "C1032") (pin "1") (pinfunction "1_1") (pintype "passive"))
      (node (ref "R2970") (pin "2") (pinfunction "2_2") (pintype "passive"))
      (node (ref "U742") (pin "6") (pinfunction "SST/nFAULT_6") (pintype "passive"))
    )
    (net (code "58") (name "Net-(U742-VCP)") (class "Default")
      (node (ref "C1031") (pin "1") (pinfunction "1_1") (pintype "passive"))
      (node (ref "R2969") (pin "2") (pinfunction "2_2") (pintype "passive"))
      (node (ref "U742") (pin "4") (pinfunction "VCP_4") (pintype "passive"))
    )
    (net (code "59") (name "RTC_CLK") (class "Default")
      (node (ref "U740") (pin "6") (pinfunction "CLKOUT_6") (pintype "passive"))
    )
    (net (code "60") (name "RTC_nINTA") (class "Default")
      (node (ref "R2984") (pin "1") (pinfunction "1_1") (pintype "passive"))
      (node (ref "R2986") (pin "1") (pinfunction "1_1") (pintype "passive"))
      (node (ref "U740") (pin "13") (pinfunction "~{INTA}_13") (pintype "passive"))
    )
    (net (code "61") (name "SYS_nRST") (class "Default")
      (node (ref "C1037") (pin "2") (pinfunction "2_2") (pintype "passive"))
      (node (ref "D628") (pin "1") (pinfunction "1_1") (pintype "passive"))
      (node (ref "P19") (pin "1") (pinfunction "1_1") (pintype "passive"))
      (node (ref "R2987") (pin "2") (pinfunction "2_2") (pintype "passive"))
    )
    (net (code "62") (name "USB2_HOST_DN") (class "Default")
      (node (ref "U735") (pin "C1") (pinfunction "CH1_OUT+_C1") (pintype "bidirectional"))
    )
    (net (code "63") (name "USB2_HOST_DP") (class "Default")
      (node (ref "U735") (pin "C2") (pinfunction "CH1_OUT-_C2") (pintype "bidirectional"))
    )
    (net (code "64") (name "USB_I2C_SCL") (class "Default")
      (node (ref "R2923") (pin "1") (pinfunction "1_1") (pintype "passive"))
    )
    (net (code "65") (name "USB_I2C_SDA") (class "Default")
      (node (ref "R2922") (pin "1") (pinfunction "1_1") (pintype "passive"))
    )
    (net (code "66") (name "V21_GPIO_IO25") (class "Default")
      (node (ref "SW3") (pin "1") (pinfunction "1_1") (pintype "passive"))
      (node (ref "TP1083") (pin "1") (pinfunction "TP_1") (pintype "passive"))
    )
    (net (code "67") (name "VBBS") (class "Default")
      (node (ref "C1036") (pin "1") (pinfunction "1_1") (pintype "passive"))
      (node (ref "U740") (pin "14") (pinfunction "BBS_14") (pintype "passive"))
    )
    (net (code "68") (name "VBUS_USB2_5V") (class "Default")
      (node (ref "C1029") (pin "1") (pinfunction "1_1") (pintype "passive"))
      (node (ref "C1030") (pin "1") (pinfunction "1_1") (pintype "passive"))
      (node (ref "D626") (pin "1") (pinfunction "1_1") (pintype "passive"))
      (node (ref "P17") (pin "1") (pinfunction "VCC_1") (pintype "passive"))
      (node (ref "U742") (pin "10") (pinfunction "OUT1_10") (pintype "passive"))
      (node (ref "U742") (pin "8") (pinfunction "OUT3_8") (pintype "passive"))
      (node (ref "U742") (pin "9") (pinfunction "OUT2_9") (pintype "passive"))
    )
    (net (code "69") (name "VCC_3V3_DEBUG") (class "Default")
      (node (ref "C1000") (pin "1") (pinfunction "1_1") (pintype "passive"))
      (node (ref "C999") (pin "1") (pinfunction "1_1") (pintype "passive"))
      (node (ref "U737") (pin "1") (pinfunction "OUT_1") (pintype "passive"))
      (node (ref "U738") (pin "2") (pinfunction "VCCB_2") (pintype "passive"))
    )
    (net (code "70") (name "VDD_3V3") (class "Default")
      (node (ref "C998") (pin "1") (pinfunction "1_1") (pintype "passive"))
      (node (ref "R2916") (pin "2") (pinfunction "2_2") (pintype "passive"))
      (node (ref "R2918") (pin "1") (pinfunction "1_1") (pintype "passive"))
      (node (ref "R2925") (pin "1") (pinfunction "1_1") (pintype "passive"))
      (node (ref "R2967") (pin "1") (pinfunction "1_1") (pintype "passive"))
      (node (ref "R2982") (pin "2") (pinfunction "2_2") (pintype "passive"))
      (node (ref "R2983") (pin "2") (pinfunction "2_2") (pintype "passive"))
      (node (ref "R2985") (pin "2") (pinfunction "2_2") (pintype "passive"))
      (node (ref "R2986") (pin "2") (pinfunction "2_2") (pintype "passive"))
      (node (ref "U738") (pin "3") (pinfunction "VCCA_3") (pintype "passive"))
    )
    (net (code "71") (name "VDD_5V") (class "Default")
      (node (ref "C1027") (pin "1") (pinfunction "1_1") (pintype "passive"))
      (node (ref "C1028") (pin "1") (pinfunction "1_1") (pintype "passive"))
      (node (ref "R2924") (pin "2") (pinfunction "2_2") (pintype "passive"))
      (node (ref "R2969") (pin "1") (pinfunction "1_1") (pintype "passive"))
      (node (ref "U742") (pin "1") (pinfunction "IN1_1") (pintype "passive"))
      (node (ref "U742") (pin "2") (pinfunction "IN2_2") (pintype "passive"))
      (node (ref "U742") (pin "3") (pinfunction "IN3_3") (pintype "passive"))
    )
    (net (code "72") (name "VLDO_3V3") (class "Default")
      (node (ref "D627") (pin "A") (pinfunction "ANODE_A") (pintype "passive"))
      (node (ref "R2976") (pin "1") (pinfunction "1_1") (pintype "passive"))
      (node (ref "R2979") (pin "1") (pinfunction "1_1") (pintype "passive"))
    )
    (net (code "73") (name "W21_GPIO_IO27") (class "Default")
      (node (ref "SW3") (pin "2") (pinfunction "2_2") (pintype "passive"))
      (node (ref "TP1084") (pin "1") (pinfunction "TP_1") (pintype "passive"))
    )
    (net (code "74") (name "unconnected-(P16-HOLE_1-PadH1)") (class "Default")
      (node (ref "P16") (pin "H1") (pinfunction "HOLE_1_H1") (pintype "passive+no_connect"))
    )
    (net (code "75") (name "unconnected-(P16-HOLE_2-PadH2)") (class "Default")
      (node (ref "P16") (pin "H2") (pinfunction "HOLE_2_H2") (pintype "passive+no_connect"))
    )
    (net (code "76") (name "unconnected-(P16-SBU1-PadA8)") (class "Default")
      (node (ref "P16") (pin "A8") (pinfunction "SBU1_A8") (pintype "passive+no_connect"))
    )
    (net (code "77") (name "unconnected-(P16-SBU2-PadB8)") (class "Default")
      (node (ref "P16") (pin "B8") (pinfunction "SBU2_B8") (pintype "passive+no_connect"))
    )
    (net (code "78") (name "unconnected-(U734-CTS0-Pad18)") (class "Default")
      (node (ref "U734") (pin "18") (pinfunction "CTS0_18") (pintype "passive+no_connect"))
    )
    (net (code "79") (name "unconnected-(U734-CTS1-Pad10)") (class "Default")
      (node (ref "U734") (pin "10") (pinfunction "CTS1_10") (pintype "passive+no_connect"))
    )
    (net (code "80") (name "unconnected-(U734-DCD0-Pad24)") (class "Default")
      (node (ref "U734") (pin "24") (pinfunction "DCD0_24") (pintype "passive+no_connect"))
    )
    (net (code "81") (name "unconnected-(U734-DCD1-Pad16)") (class "Default")
      (node (ref "U734") (pin "16") (pinfunction "DCD1_16") (pintype "passive+no_connect"))
    )
    (net (code "82") (name "unconnected-(U734-DI0-Pad1)") (class "Default")
      (node (ref "U734") (pin "1") (pinfunction "DI0_1") (pintype "passive+no_connect"))
    )
    (net (code "83") (name "unconnected-(U734-DI1-Pad17)") (class "Default")
      (node (ref "U734") (pin "17") (pinfunction "DI1_17") (pintype "passive+no_connect"))
    )
    (net (code "84") (name "unconnected-(U734-DSR0-Pad22)") (class "Default")
      (node (ref "U734") (pin "22") (pinfunction "DSR0_22") (pintype "passive+no_connect"))
    )
    (net (code "85") (name "unconnected-(U734-DSR1-Pad14)") (class "Default")
      (node (ref "U734") (pin "14") (pinfunction "DSR1_14") (pintype "passive+no_connect"))
    )
    (net (code "86") (name "unconnected-(U734-DTR0{slash}TNOW0-Pad23)") (class "Default")
      (node (ref "U734") (pin "23") (pinfunction "DTR0/TNOW0_23") (pintype "passive+no_connect"))
    )
    (net (code "87") (name "unconnected-(U734-DTR1{slash}TNOW1-Pad15)") (class "Default")
      (node (ref "U734") (pin "15") (pinfunction "DTR1/TNOW1_15") (pintype "passive+no_connect"))
    )
    (net (code "88") (name "unconnected-(U734-RTS0-Pad19)") (class "Default")
      (node (ref "U734") (pin "19") (pinfunction "RTS0_19") (pintype "passive+no_connect"))
    )
    (net (code "89") (name "unconnected-(U734-RTS1-Pad11)") (class "Default")
      (node (ref "U734") (pin "11") (pinfunction "RTS1_11") (pintype "passive+no_connect"))
    )
    (net (code "90") (name "unconnected-(U734-~{RST}-Pad9)") (class "Default")
      (node (ref "U734") (pin "9") (pinfunction "~{RST}_9") (pintype "passive+no_connect"))
    )
  )
)
